# Expansion_Board.net
KiCad netlist of a schematic drawn in Altium Designer
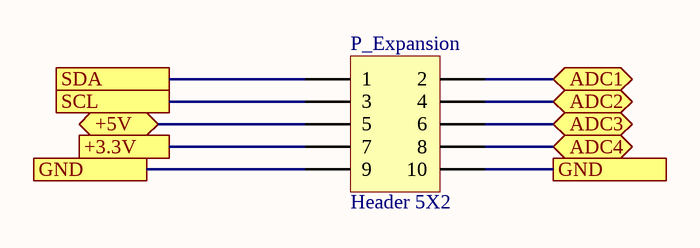
[diagram p0: Expansion Board.SchDoc]

(export (version "E")
  (design (tool "Eeschema 10.0.6"))
  (components
    (comp (ref "P_Expansion")
      (value "Header 5X2")
      (footprint "HDR2X5")
      (description "Header, 5-Pin, Dual row")
      (fields (field (name "PUBLISHER") "Altium Limited"))
      (libsource (lib "Miscellaneous Connectors") (part "Header 5X2"))
    )
  )
  (nets
    (net (code "1") (name "/+3.3V") (class "Default")
      (node (ref "P_Expansion") (pin "7") (pinfunction "7_7") (pintype "passive"))
    )
    (net (code "2") (name "/+5V") (class "Default")
      (node (ref "P_Expansion") (pin "5") (pinfunction "5_5") (pintype "passive"))
    )
    (net (code "3") (name "/ADC1") (class "Default")
      (node (ref "P_Expansion") (pin "2") (pinfunction "2_2") (pintype "passive"))
    )
    (net (code "4") (name "/ADC2") (class "Default")
      (node (ref "P_Expansion") (pin "4") (pinfunction "4_4") (pintype "passive"))
    )
    (net (code "5") (name "/ADC3") (class "Default")
      (node (ref "P_Expansion") (pin "6") (pinfunction "6_6") (pintype "passive"))
    )
    (net (code "6") (name "/ADC4") (class "Default")
      (node (ref "P_Expansion") (pin "8") (pinfunction "8_8") (pintype "passive"))
    )
    (net (code "7") (name "/GND") (class "Default")
      (node (ref "P_Expansion") (pin "10") (pinfunction "10_10") (pintype "passive"))
      (node (ref "P_Expansion") (pin "9") (pinfunction "9_9") (pintype "passive"))
    )
    (net (code "8") (name "/SCL") (class "Default")
      (node (ref "P_Expansion") (pin "3") (pinfunction "3_3") (pintype "passive"))
    )
    (net (code "9") (name "/SDA") (class "Default")
      (node (ref "P_Expansion") (pin "1") (pinfunction "1_1") (pintype "passive"))
    )
  )
)
